# HomeAtion_RemoteDHT.net
KiCad netlist of a schematic drawn in EAGLE
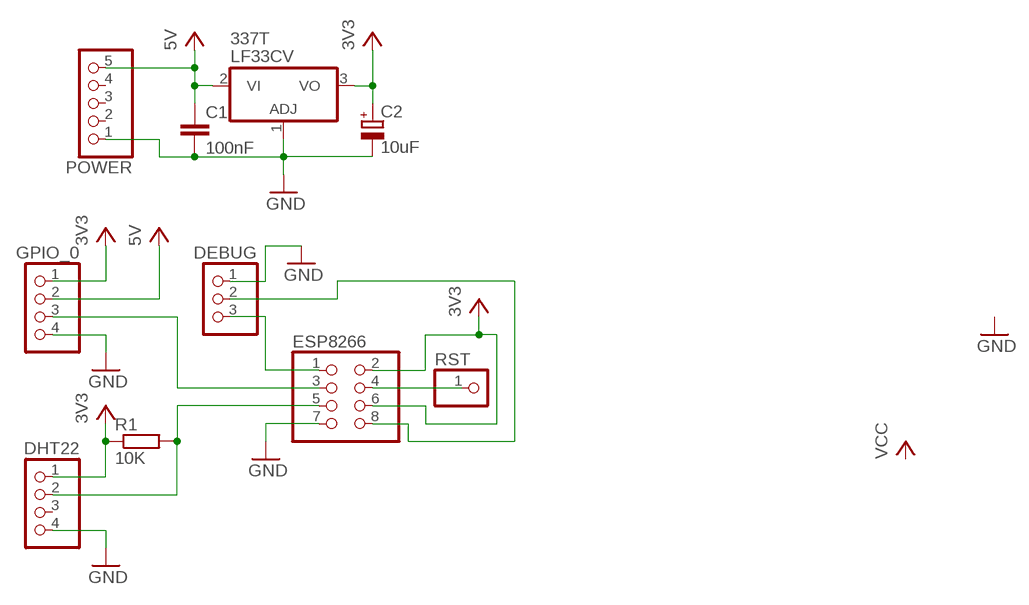
[diagram p0: schematic, sheet 1]

(export (version "E")
  (design (tool "Eeschema 10.0.6"))
  (components
    (comp (ref "C1")
      (value "100nF")
      (footprint "eagle-import:C2.5-5")
      (libsource (lib "eagle-import") (part "C2.5/5"))
    )
    (comp (ref "C2")
      (value "10uF")
      (footprint "eagle-import:B45181A")
      (libsource (lib "eagle-import") (part "CPOL-EUB45181A"))
    )
    (comp (ref "DEBUG")
      (value "PINHD-1X3")
      (footprint "eagle-import:1X03")
      (libsource (lib "eagle-import") (part "PINHD-1X3"))
    )
    (comp (ref "DHT22")
      (value "PINHD-1X4")
      (footprint "eagle-import:1X04")
      (libsource (lib "eagle-import") (part "PINHD-1X4"))
    )
    (comp (ref "ESP8266")
      (value "PINHD-2X4")
      (footprint "eagle-import:2X04")
      (libsource (lib "eagle-import") (part "PINHD-2X4"))
    )
    (comp (ref "GPIO_0")
      (value "PINHD-1X4")
      (footprint "eagle-import:1X04")
      (libsource (lib "eagle-import") (part "PINHD-1X4"))
    )
    (comp (ref "LF33CV")
      (value "337T")
      (footprint "eagle-import:TO220H")
      (libsource (lib "eagle-import") (part "337T"))
    )
    (comp (ref "POWER")
      (value "PINHD-1X5")
      (footprint "eagle-import:1X05")
      (libsource (lib "eagle-import") (part "PINHD-1X5"))
    )
    (comp (ref "R1")
      (value "10K")
      (footprint "eagle-import:0204_7")
      (libsource (lib "eagle-import") (part "R-EU_0204/7"))
    )
    (comp (ref "RST")
      (value "PINHD-1X1")
      (footprint "eagle-import:1X01")
      (libsource (lib "eagle-import") (part "PINHD-1X1"))
    )
  )
  (nets
    (net (code "1") (name "3V3") (class "Default")
      (node (ref "C1") (pin "1") (pinfunction "1_1") (pintype "passive"))
      (node (ref "C2") (pin "+") (pinfunction "+_+") (pintype "passive"))
      (node (ref "DHT22") (pin "1") (pinfunction "1_1") (pintype "passive"))
      (node (ref "ESP8266") (pin "2") (pinfunction "2_2") (pintype "passive"))
      (node (ref "ESP8266") (pin "6") (pinfunction "6_6") (pintype "passive"))
      (node (ref "GPIO_0") (pin "1") (pinfunction "1_1") (pintype "passive"))
      (node (ref "GPIO_0") (pin "2") (pinfunction "2_2") (pintype "passive"))
      (node (ref "LF33CV") (pin "2") (pinfunction "VI_2") (pintype "input"))
      (node (ref "LF33CV") (pin "3") (pinfunction "VO_3") (pintype "passive"))
      (node (ref "POWER") (pin "5") (pinfunction "5_5") (pintype "passive"))
      (node (ref "R1") (pin "1") (pinfunction "1_1") (pintype "passive"))
    )
    (net (code "2") (name "GND") (class "Default")
      (node (ref "C1") (pin "2") (pinfunction "2_2") (pintype "passive"))
      (node (ref "C2") (pin "-") (pinfunction "-_-") (pintype "passive"))
      (node (ref "DEBUG") (pin "1") (pinfunction "1_1") (pintype "passive"))
      (node (ref "DHT22") (pin "4") (pinfunction "4_4") (pintype "passive"))
      (node (ref "ESP8266") (pin "7") (pinfunction "7_7") (pintype "passive"))
      (node (ref "GPIO_0") (pin "4") (pinfunction "4_4") (pintype "passive"))
      (node (ref "LF33CV") (pin "1") (pinfunction "ADJ_1") (pintype "input"))
      (node (ref "POWER") (pin "1") (pinfunction "1_1") (pintype "passive"))
    )
    (net (code "3") (name "Net-(DEBUG-Pad2)") (class "Default")
      (node (ref "DEBUG") (pin "2") (pinfunction "2_2") (pintype "passive"))
      (node (ref "ESP8266") (pin "8") (pinfunction "8_8") (pintype "passive"))
    )
    (net (code "4") (name "Net-(DEBUG-Pad3)") (class "Default")
      (node (ref "DEBUG") (pin "3") (pinfunction "3_3") (pintype "passive"))
      (node (ref "ESP8266") (pin "1") (pinfunction "1_1") (pintype "passive"))
    )
    (net (code "5") (name "Net-(DHT22-Pad2)") (class "Default")
      (node (ref "DHT22") (pin "2") (pinfunction "2_2") (pintype "passive"))
      (node (ref "ESP8266") (pin "5") (pinfunction "5_5") (pintype "passive"))
      (node (ref "R1") (pin "2") (pinfunction "2_2") (pintype "passive"))
    )
    (net (code "6") (name "Net-(ESP8266-Pad3)") (class "Default")
      (node (ref "ESP8266") (pin "3") (pinfunction "3_3") (pintype "passive"))
      (node (ref "GPIO_0") (pin "3") (pinfunction "3_3") (pintype "passive"))
    )
    (net (code "7") (name "Net-(ESP8266-Pad4)") (class "Default")
      (node (ref "ESP8266") (pin "4") (pinfunction "4_4") (pintype "passive"))
      (node (ref "RST") (pin "1") (pinfunction "1_1") (pintype "passive"))
    )
    (net (code "8") (name "unconnected-(DHT22-Pad3)") (class "Default")
      (node (ref "DHT22") (pin "3") (pinfunction "3_3") (pintype "passive"))
    )
    (net (code "9") (name "unconnected-(POWER-Pad2)") (class "Default")
      (node (ref "POWER") (pin "2") (pinfunction "2_2") (pintype "passive"))
    )
    (net (code "10") (name "unconnected-(POWER-Pad3)") (class "Default")
      (node (ref "POWER") (pin "3") (pinfunction "3_3") (pintype "passive"))
    )
    (net (code "11") (name "unconnected-(POWER-Pad4)") (class "Default")
      (node (ref "POWER") (pin "4") (pinfunction "4_4") (pintype "passive"))
    )
  )
)
